# IF.net
KiCad netlist of a schematic drawn in Altium Designer
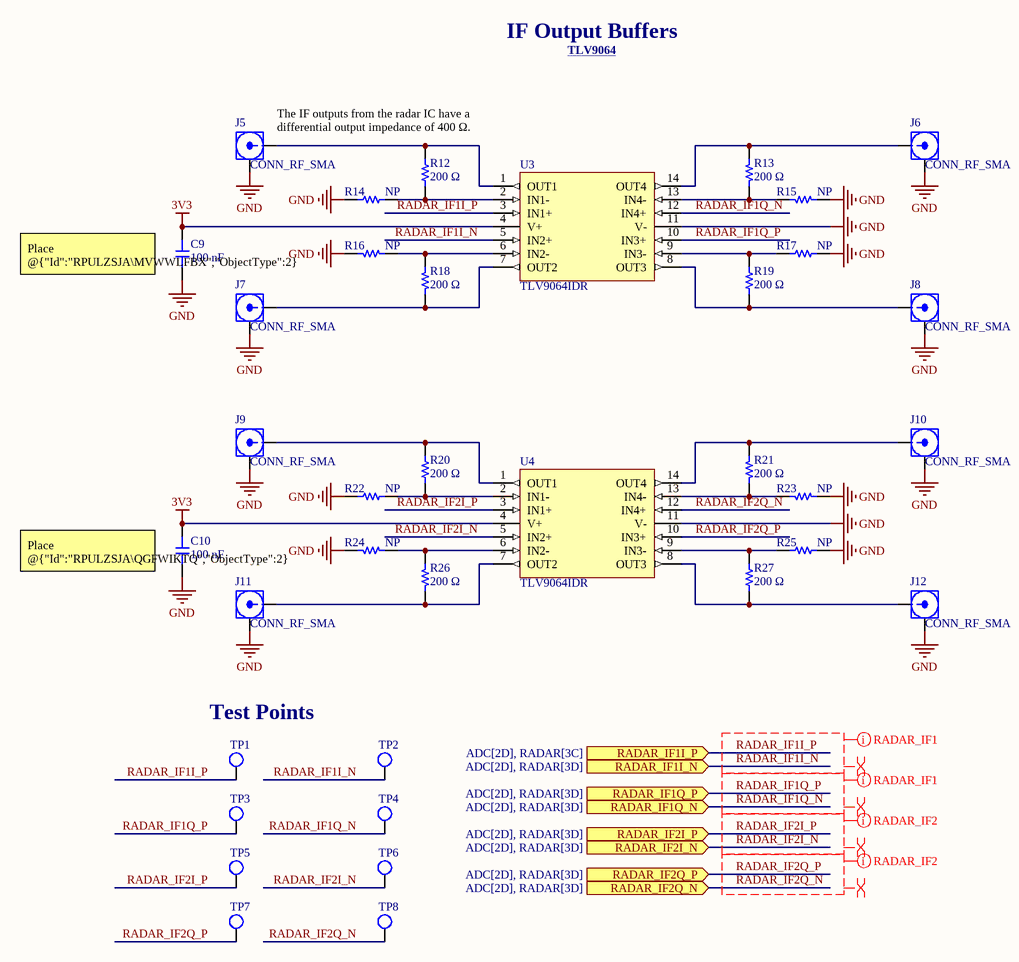
[diagram p0: IF.SchDoc]

(export (version "E")
  (design (tool "Eeschema 10.0.6"))
  (components
    (comp (ref "C9")
      (value "100 nF")
      (footprint "CAP_0402")
      (description "25V 100nF X7R ±10% 0402 Multilayer Ceramic Capacitors MLCC - SMD/SMT ROHS")
      (fields
        (field (name "MANUFACTURER") "Samsung Electro-Mechanics")
        (field (name "MANUFACTURER PART NUMBER") "CL05B104KA5NNNC")
      )
      (libsource (lib "Titan") (part "CAP"))
    )
    (comp (ref "C10")
      (value "100 nF")
      (footprint "CAP_0402")
      (description "25V 100nF X7R ±10% 0402 Multilayer Ceramic Capacitors MLCC - SMD/SMT ROHS")
      (fields
        (field (name "MANUFACTURER") "Samsung Electro-Mechanics")
        (field (name "MANUFACTURER PART NUMBER") "CL05B104KA5NNNC")
      )
      (libsource (lib "Titan") (part "CAP"))
    )
    (comp (ref "J5")
      (value "CONN_RF_SMA")
      (footprint "SMA-J-P-H-ST-TH1")
      (description "RF / Coaxial Connector, SMA Coaxial, Straight Jack, Through Hole Vertical, 50 ohm")
      (fields
        (field (name "MANUFACTURER") "Samtec")
        (field (name "MANUFACTURER PART NUMBER") "SMA-J-P-H-ST-TH1")
      )
      (libsource (lib "Titan") (part "CONN_RF_SMA"))
    )
    (comp (ref "J6")
      (value "CONN_RF_SMA")
      (footprint "SMA-J-P-H-ST-TH1")
      (description "RF / Coaxial Connector, SMA Coaxial, Straight Jack, Through Hole Vertical, 50 ohm")
      (fields
        (field (name "MANUFACTURER") "Samtec")
        (field (name "MANUFACTURER PART NUMBER") "SMA-J-P-H-ST-TH1")
      )
      (libsource (lib "Titan") (part "CONN_RF_SMA"))
    )
    (comp (ref "J7")
      (value "CONN_RF_SMA")
      (footprint "SMA-J-P-H-ST-TH1")
      (description "RF / Coaxial Connector, SMA Coaxial, Straight Jack, Through Hole Vertical, 50 ohm")
      (fields
        (field (name "MANUFACTURER") "Samtec")
        (field (name "MANUFACTURER PART NUMBER") "SMA-J-P-H-ST-TH1")
      )
      (libsource (lib "Titan") (part "CONN_RF_SMA"))
    )
    (comp (ref "J8")
      (value "CONN_RF_SMA")
      (footprint "SMA-J-P-H-ST-TH1")
      (description "RF / Coaxial Connector, SMA Coaxial, Straight Jack, Through Hole Vertical, 50 ohm")
      (fields
        (field (name "MANUFACTURER") "Samtec")
        (field (name "MANUFACTURER PART NUMBER") "SMA-J-P-H-ST-TH1")
      )
      (libsource (lib "Titan") (part "CONN_RF_SMA"))
    )
    (comp (ref "J9")
      (value "CONN_RF_SMA")
      (footprint "SMA-J-P-H-ST-TH1")
      (description "RF / Coaxial Connector, SMA Coaxial, Straight Jack, Through Hole Vertical, 50 ohm")
      (fields
        (field (name "MANUFACTURER") "Samtec")
        (field (name "MANUFACTURER PART NUMBER") "SMA-J-P-H-ST-TH1")
      )
      (libsource (lib "Titan") (part "CONN_RF_SMA"))
    )
    (comp (ref "J10")
      (value "CONN_RF_SMA")
      (footprint "SMA-J-P-H-ST-TH1")
      (description "RF / Coaxial Connector, SMA Coaxial, Straight Jack, Through Hole Vertical, 50 ohm")
      (fields
        (field (name "MANUFACTURER") "Samtec")
        (field (name "MANUFACTURER PART NUMBER") "SMA-J-P-H-ST-TH1")
      )
      (libsource (lib "Titan") (part "CONN_RF_SMA"))
    )
    (comp (ref "J11")
      (value "CONN_RF_SMA")
      (footprint "SMA-J-P-H-ST-TH1")
      (description "RF / Coaxial Connector, SMA Coaxial, Straight Jack, Through Hole Vertical, 50 ohm")
      (fields
        (field (name "MANUFACTURER") "Samtec")
        (field (name "MANUFACTURER PART NUMBER") "SMA-J-P-H-ST-TH1")
      )
      (libsource (lib "Titan") (part "CONN_RF_SMA"))
    )
    (comp (ref "J12")
      (value "CONN_RF_SMA")
      (footprint "SMA-J-P-H-ST-TH1")
      (description "RF / Coaxial Connector, SMA Coaxial, Straight Jack, Through Hole Vertical, 50 ohm")
      (fields
        (field (name "MANUFACTURER") "Samtec")
        (field (name "MANUFACTURER PART NUMBER") "SMA-J-P-H-ST-TH1")
      )
      (libsource (lib "Titan") (part "CONN_RF_SMA"))
    )
    (comp (ref "R12")
      (value "200 Ω")
      (footprint "RES_0603")
      (description "100mW Thick Film Resistors 75V ±100ppm/℃ ±1% 200Ω 0603 Chip Resistor - Surface Mount ROHS")
      (fields
        (field (name "MANUFACTURER") "Yageo")
        (field (name "MANUFACTURER PART NUMBER") "RC0603FR-07200RL")
      )
      (libsource (lib "Titan") (part "RES"))
    )
    (comp (ref "R13")
      (value "200 Ω")
      (footprint "RES_0603")
      (description "100mW Thick Film Resistors 75V ±100ppm/℃ ±1% 200Ω 0603 Chip Resistor - Surface Mount ROHS")
      (fields
        (field (name "MANUFACTURER") "Yageo")
        (field (name "MANUFACTURER PART NUMBER") "RC0603FR-07200RL")
      )
      (libsource (lib "Titan") (part "RES"))
    )
    (comp (ref "R14")
      (value "NP")
      (footprint "RES_0603")
      (description "Resistor SMD Generic")
      (libsource (lib "Titan") (part "RES"))
    )
    (comp (ref "R15")
      (value "NP")
      (footprint "RES_0603")
      (description "Resistor SMD Generic")
      (libsource (lib "Titan") (part "RES"))
    )
    (comp (ref "R16")
      (value "NP")
      (footprint "RES_0603")
      (description "Resistor SMD Generic")
      (libsource (lib "Titan") (part "RES"))
    )
    (comp (ref "R17")
      (value "NP")
      (footprint "RES_0603")
      (description "Resistor SMD Generic")
      (libsource (lib "Titan") (part "RES"))
    )
    (comp (ref "R18")
      (value "200 Ω")
      (footprint "RES_0603")
      (description "100mW Thick Film Resistors 75V ±100ppm/℃ ±1% 200Ω 0603 Chip Resistor - Surface Mount ROHS")
      (fields
        (field (name "MANUFACTURER") "Yageo")
        (field (name "MANUFACTURER PART NUMBER") "RC0603FR-07200RL")
      )
      (libsource (lib "Titan") (part "RES"))
    )
    (comp (ref "R19")
      (value "200 Ω")
      (footprint "RES_0603")
      (description "100mW Thick Film Resistors 75V ±100ppm/℃ ±1% 200Ω 0603 Chip Resistor - Surface Mount ROHS")
      (fields
        (field (name "MANUFACTURER") "Yageo")
        (field (name "MANUFACTURER PART NUMBER") "RC0603FR-07200RL")
      )
      (libsource (lib "Titan") (part "RES"))
    )
    (comp (ref "R20")
      (value "200 Ω")
      (footprint "RES_0603")
      (description "100mW Thick Film Resistors 75V ±100ppm/℃ ±1% 200Ω 0603 Chip Resistor - Surface Mount ROHS")
      (fields
        (field (name "MANUFACTURER") "Yageo")
        (field (name "MANUFACTURER PART NUMBER") "RC0603FR-07200RL")
      )
      (libsource (lib "Titan") (part "RES"))
    )
    (comp (ref "R21")
      (value "200 Ω")
      (footprint "RES_0603")
      (description "100mW Thick Film Resistors 75V ±100ppm/℃ ±1% 200Ω 0603 Chip Resistor - Surface Mount ROHS")
      (fields
        (field (name "MANUFACTURER") "Yageo")
        (field (name "MANUFACTURER PART NUMBER") "RC0603FR-07200RL")
      )
      (libsource (lib "Titan") (part "RES"))
    )
    (comp (ref "R22")
      (value "NP")
      (footprint "RES_0603")
      (description "Resistor SMD Generic")
      (libsource (lib "Titan") (part "RES"))
    )
    (comp (ref "R23")
      (value "NP")
      (footprint "RES_0603")
      (description "Resistor SMD Generic")
      (libsource (lib "Titan") (part "RES"))
    )
    (comp (ref "R24")
      (value "NP")
      (footprint "RES_0603")
      (description "Resistor SMD Generic")
      (libsource (lib "Titan") (part "RES"))
    )
    (comp (ref "R25")
      (value "NP")
      (footprint "RES_0603")
      (description "Resistor SMD Generic")
      (libsource (lib "Titan") (part "RES"))
    )
    (comp (ref "R26")
      (value "200 Ω")
      (footprint "RES_0603")
      (description "100mW Thick Film Resistors 75V ±100ppm/℃ ±1% 200Ω 0603 Chip Resistor - Surface Mount ROHS")
      (fields
        (field (name "MANUFACTURER") "Yageo")
        (field (name "MANUFACTURER PART NUMBER") "RC0603FR-07200RL")
      )
      (libsource (lib "Titan") (part "RES"))
    )
    (comp (ref "R27")
      (value "200 Ω")
      (footprint "RES_0603")
      (description "100mW Thick Film Resistors 75V ±100ppm/℃ ±1% 200Ω 0603 Chip Resistor - Surface Mount ROHS")
      (fields
        (field (name "MANUFACTURER") "Yageo")
        (field (name "MANUFACTURER PART NUMBER") "RC0603FR-07200RL")
      )
      (libsource (lib "Titan") (part "RES"))
    )
    (comp (ref "TP1")
      (value "TEST_POINT")
      (footprint "TEST_POINT")
      (description "Test Point Generic")
      (libsource (lib "Titan") (part "TEST_POINT"))
    )
    (comp (ref "TP2")
      (value "TEST_POINT")
      (footprint "TEST_POINT")
      (description "Test Point Generic")
      (libsource (lib "Titan") (part "TEST_POINT"))
    )
    (comp (ref "TP3")
      (value "TEST_POINT")
      (footprint "TEST_POINT")
      (description "Test Point Generic")
      (libsource (lib "Titan") (part "TEST_POINT"))
    )
    (comp (ref "TP4")
      (value "TEST_POINT")
      (footprint "TEST_POINT")
      (description "Test Point Generic")
      (libsource (lib "Titan") (part "TEST_POINT"))
    )
    (comp (ref "TP5")
      (value "TEST_POINT")
      (footprint "TEST_POINT")
      (description "Test Point Generic")
      (libsource (lib "Titan") (part "TEST_POINT"))
    )
    (comp (ref "TP6")
      (value "TEST_POINT")
      (footprint "TEST_POINT")
      (description "Test Point Generic")
      (libsource (lib "Titan") (part "TEST_POINT"))
    )
    (comp (ref "TP7")
      (value "TEST_POINT")
      (footprint "TEST_POINT")
      (description "Test Point Generic")
      (libsource (lib "Titan") (part "TEST_POINT"))
    )
    (comp (ref "TP8")
      (value "TEST_POINT")
      (footprint "TEST_POINT")
      (description "Test Point Generic")
      (libsource (lib "Titan") (part "TEST_POINT"))
    )
    (comp (ref "U3")
      (value "TLV9064IDR")
      (footprint "TLV9064IDR")
      (description "Quad, 5.5-V, 10-MHz, RRIO operational amplifier for cost-optimized applications 14-SOIC -40 to 125")
      (fields (field (name "MANUFACTURER") "Texas Instruments"))
      (libsource (lib "Titan") (part "TLV9064IDR"))
    )
    (comp (ref "U4")
      (value "TLV9064IDR")
      (footprint "TLV9064IDR")
      (description "Quad, 5.5-V, 10-MHz, RRIO operational amplifier for cost-optimized applications 14-SOIC -40 to 125")
      (fields (field (name "MANUFACTURER") "Texas Instruments"))
      (libsource (lib "Titan") (part "TLV9064IDR"))
    )
  )
  (nets
    (net (code "1") (name "/RADAR_IF1I_N") (class "Default")
      (node (ref "TP2") (pin "1") (pintype "passive"))
      (node (ref "U3") (pin "5") (pinfunction "IN2+_5") (pintype "input"))
    )
    (net (code "2") (name "/RADAR_IF1I_P") (class "Default")
      (node (ref "TP1") (pin "1") (pintype "passive"))
      (node (ref "U3") (pin "3") (pinfunction "IN1+_3") (pintype "input"))
    )
    (net (code "3") (name "/RADAR_IF1Q_N") (class "Default")
      (node (ref "TP4") (pin "1") (pintype "passive"))
      (node (ref "U3") (pin "12") (pinfunction "IN4+_12") (pintype "input"))
    )
    (net (code "4") (name "/RADAR_IF1Q_P") (class "Default")
      (node (ref "TP3") (pin "1") (pintype "passive"))
      (node (ref "U3") (pin "10") (pinfunction "IN3+_10") (pintype "input"))
    )
    (net (code "5") (name "/RADAR_IF2I_N") (class "Default")
      (node (ref "TP6") (pin "1") (pintype "passive"))
      (node (ref "U4") (pin "5") (pinfunction "IN2+_5") (pintype "input"))
    )
    (net (code "6") (name "/RADAR_IF2I_P") (class "Default")
      (node (ref "TP5") (pin "1") (pintype "passive"))
      (node (ref "U4") (pin "3") (pinfunction "IN1+_3") (pintype "input"))
    )
    (net (code "7") (name "/RADAR_IF2Q_N") (class "Default")
      (node (ref "TP8") (pin "1") (pintype "passive"))
      (node (ref "U4") (pin "12") (pinfunction "IN4+_12") (pintype "input"))
    )
    (net (code "8") (name "/RADAR_IF2Q_P") (class "Default")
      (node (ref "TP7") (pin "1") (pintype "passive"))
      (node (ref "U4") (pin "10") (pinfunction "IN3+_10") (pintype "input"))
    )
    (net (code "9") (name "3V3") (class "Default")
      (node (ref "C10") (pin "1") (pintype "passive"))
      (node (ref "C9") (pin "1") (pintype "passive"))
      (node (ref "U3") (pin "4") (pinfunction "V+_4") (pintype "power_in"))
      (node (ref "U4") (pin "4") (pinfunction "V+_4") (pintype "power_in"))
    )
    (net (code "10") (name "GND") (class "Default")
      (node (ref "C10") (pin "2") (pintype "passive"))
      (node (ref "C9") (pin "2") (pintype "passive"))
      (node (ref "J10") (pin "2") (pintype "passive"))
      (node (ref "J11") (pin "2") (pintype "passive"))
      (node (ref "J12") (pin "2") (pintype "passive"))
      (node (ref "J5") (pin "2") (pintype "passive"))
      (node (ref "J6") (pin "2") (pintype "passive"))
      (node (ref "J7") (pin "2") (pintype "passive"))
      (node (ref "J8") (pin "2") (pintype "passive"))
      (node (ref "J9") (pin "2") (pintype "passive"))
      (node (ref "R14") (pin "2") (pintype "passive"))
      (node (ref "R15") (pin "2") (pintype "passive"))
      (node (ref "R16") (pin "2") (pintype "passive"))
      (node (ref "R17") (pin "2") (pintype "passive"))
      (node (ref "R22") (pin "2") (pintype "passive"))
      (node (ref "R23") (pin "2") (pintype "passive"))
      (node (ref "R24") (pin "2") (pintype "passive"))
      (node (ref "R25") (pin "2") (pintype "passive"))
      (node (ref "U3") (pin "11") (pinfunction "V-_11") (pintype "power_in"))
      (node (ref "U4") (pin "11") (pinfunction "V-_11") (pintype "power_in"))
    )
    (net (code "11") (name "Net-(U3-IN1-)") (class "Default")
      (node (ref "R12") (pin "1") (pintype "passive"))
      (node (ref "R14") (pin "1") (pintype "passive"))
      (node (ref "U3") (pin "2") (pinfunction "IN1-_2") (pintype "input"))
    )
    (net (code "12") (name "Net-(U3-IN2-)") (class "Default")
      (node (ref "R16") (pin "1") (pintype "passive"))
      (node (ref "R18") (pin "1") (pintype "passive"))
      (node (ref "U3") (pin "6") (pinfunction "IN2-_6") (pintype "input"))
    )
    (net (code "13") (name "Net-(U3-IN3-)") (class "Default")
      (node (ref "R17") (pin "1") (pintype "passive"))
      (node (ref "R19") (pin "1") (pintype "passive"))
      (node (ref "U3") (pin "9") (pinfunction "IN3-_9") (pintype "input"))
    )
    (net (code "14") (name "Net-(U3-IN4-)") (class "Default")
      (node (ref "R13") (pin "1") (pintype "passive"))
      (node (ref "R15") (pin "1") (pintype "passive"))
      (node (ref "U3") (pin "13") (pinfunction "IN4-_13") (pintype "input"))
    )
    (net (code "15") (name "Net-(U3-OUT1)") (class "Default")
      (node (ref "J5") (pin "1") (pintype "passive"))
      (node (ref "R12") (pin "2") (pintype "passive"))
      (node (ref "U3") (pin "1") (pinfunction "OUT1_1") (pintype "output"))
    )
    (net (code "16") (name "Net-(U3-OUT2)") (class "Default")
      (node (ref "J7") (pin "1") (pintype "passive"))
      (node (ref "R18") (pin "2") (pintype "passive"))
      (node (ref "U3") (pin "7") (pinfunction "OUT2_7") (pintype "output"))
    )
    (net (code "17") (name "Net-(U3-OUT3)") (class "Default")
      (node (ref "J8") (pin "1") (pintype "passive"))
      (node (ref "R19") (pin "2") (pintype "passive"))
      (node (ref "U3") (pin "8") (pinfunction "OUT3_8") (pintype "output"))
    )
    (net (code "18") (name "Net-(U3-OUT4)") (class "Default")
      (node (ref "J6") (pin "1") (pintype "passive"))
      (node (ref "R13") (pin "2") (pintype "passive"))
      (node (ref "U3") (pin "14") (pinfunction "OUT4_14") (pintype "output"))
    )
    (net (code "19") (name "Net-(U4-IN1-)") (class "Default")
      (node (ref "R20") (pin "1") (pintype "passive"))
      (node (ref "R22") (pin "1") (pintype "passive"))
      (node (ref "U4") (pin "2") (pinfunction "IN1-_2") (pintype "input"))
    )
    (net (code "20") (name "Net-(U4-IN2-)") (class "Default")
      (node (ref "R24") (pin "1") (pintype "passive"))
      (node (ref "R26") (pin "1") (pintype "passive"))
      (node (ref "U4") (pin "6") (pinfunction "IN2-_6") (pintype "input"))
    )
    (net (code "21") (name "Net-(U4-IN3-)") (class "Default")
      (node (ref "R25") (pin "1") (pintype "passive"))
      (node (ref "R27") (pin "1") (pintype "passive"))
      (node (ref "U4") (pin "9") (pinfunction "IN3-_9") (pintype "input"))
    )
    (net (code "22") (name "Net-(U4-IN4-)") (class "Default")
      (node (ref "R21") (pin "1") (pintype "passive"))
      (node (ref "R23") (pin "1") (pintype "passive"))
      (node (ref "U4") (pin "13") (pinfunction "IN4-_13") (pintype "input"))
    )
    (net (code "23") (name "Net-(U4-OUT1)") (class "Default")
      (node (ref "J9") (pin "1") (pintype "passive"))
      (node (ref "R20") (pin "2") (pintype "passive"))
      (node (ref "U4") (pin "1") (pinfunction "OUT1_1") (pintype "output"))
    )
    (net (code "24") (name "Net-(U4-OUT2)") (class "Default")
      (node (ref "J11") (pin "1") (pintype "passive"))
      (node (ref "R26") (pin "2") (pintype "passive"))
      (node (ref "U4") (pin "7") (pinfunction "OUT2_7") (pintype "output"))
    )
    (net (code "25") (name "Net-(U4-OUT3)") (class "Default")
      (node (ref "J12") (pin "1") (pintype "passive"))
      (node (ref "R27") (pin "2") (pintype "passive"))
      (node (ref "U4") (pin "8") (pinfunction "OUT3_8") (pintype "output"))
    )
    (net (code "26") (name "Net-(U4-OUT4)") (class "Default")
      (node (ref "J10") (pin "1") (pintype "passive"))
      (node (ref "R21") (pin "2") (pintype "passive"))
      (node (ref "U4") (pin "14") (pinfunction "OUT4_14") (pintype "output"))
    )
  )
)
